# EDA-Robot_V1_3.net
KiCad netlist of a schematic drawn in EasyEDA Pro
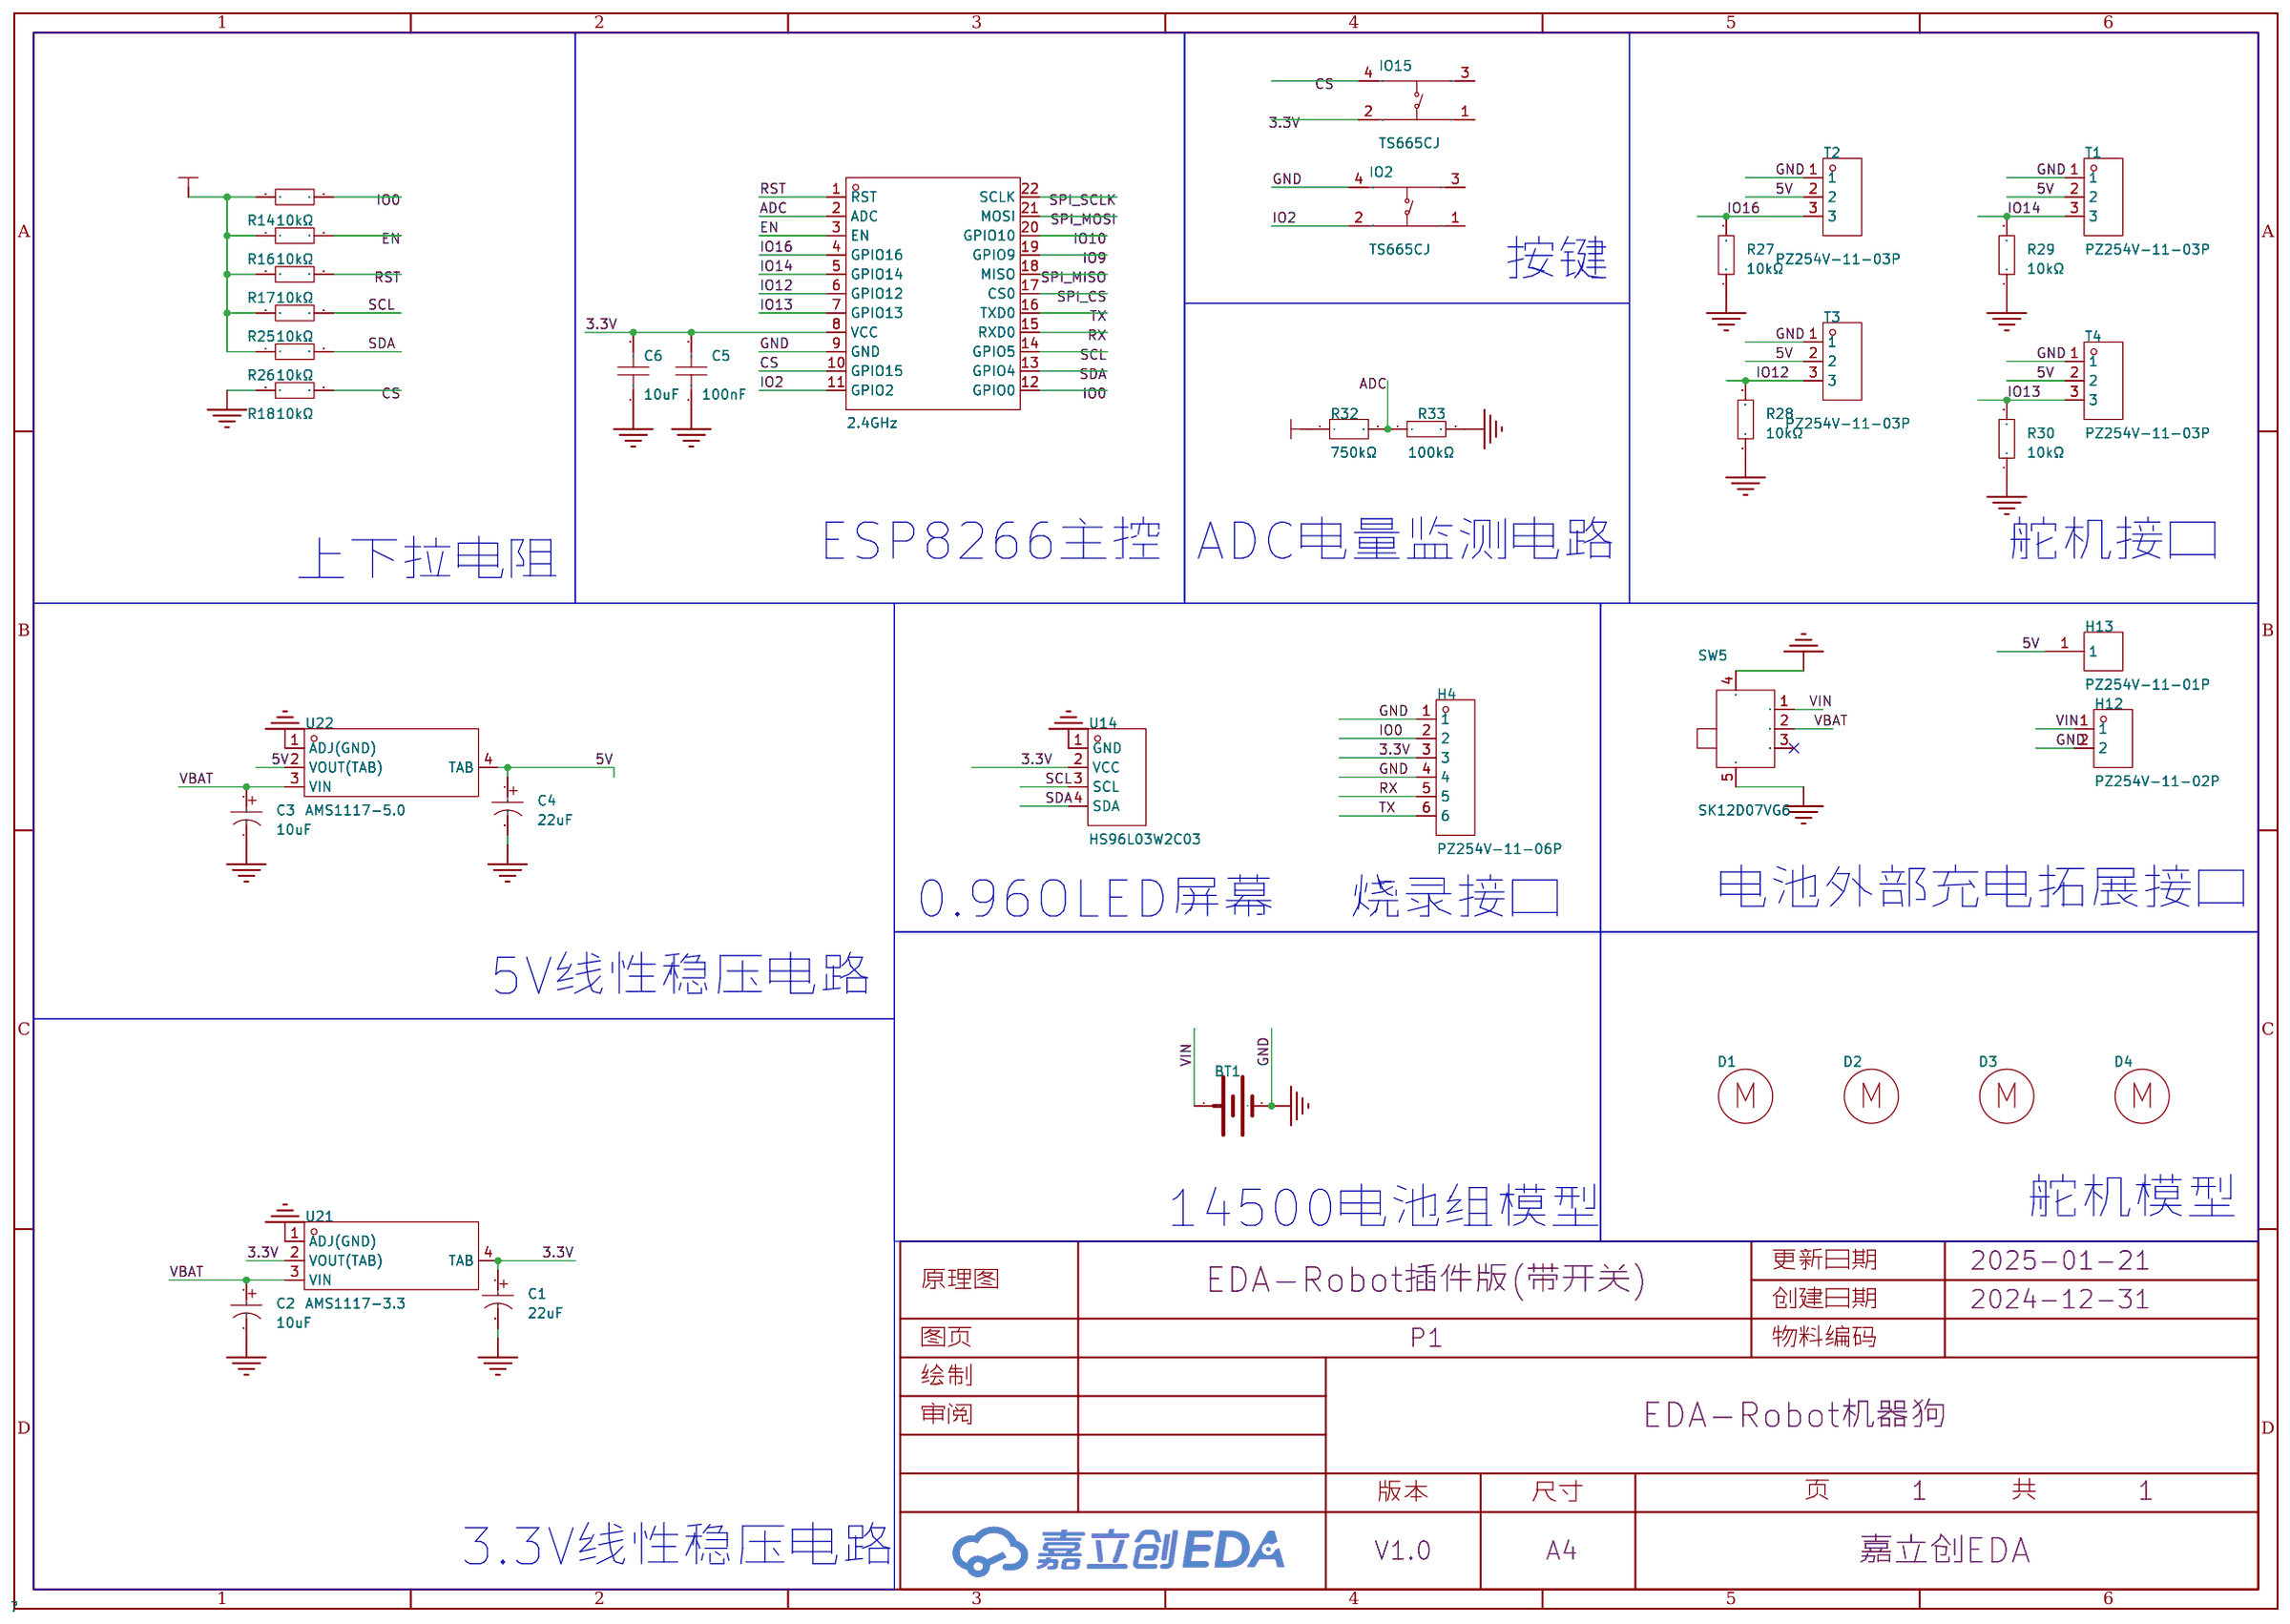
[diagram p0: schematic sheet]

(export (version "E")
  (design (tool "Eeschema 10.0.6"))
  (components
    (comp (ref "BT1")
      (value "~")
      (footprint "easyedapro:14500电池盒*2")
      (description "连接器类型:电池底座;适用电池规格:CR1220;触头材质:磷青铜;工作温度范围:-25°C~+85°C;")
      (libsource (lib "easyedapro") (part "2节串联14500电池组"))
    )
    (comp (ref "C1")
      (value "22uF")
      (footprint "easyedapro:CAP-TH_BD4.0-P1.50-D0.8-FD")
      (description "容值:10uF;精度:±20%;额定电压:25V;纹波电流:29mA@120Hz;等效串联电阻:-;")
      (fields
        (field (name "Manufacturer Part") "KS226M025C07RR0VH2FP0")
        (field (name "Manufacturer") "CX(承兴)")
      )
      (libsource (lib "easyedapro") (part "10uF 25V 4*7"))
    )
    (comp (ref "C2")
      (value "10uF")
      (footprint "easyedapro:CAP-TH_BD4.0-P1.50-D0.8-FD")
      (description "容值:10uF;精度:±20%;额定电压:25V;纹波电流:29mA@120Hz;等效串联电阻:-;")
      (fields
        (field (name "Manufacturer Part") "KS106M025C07RR0VH2FP0")
        (field (name "Manufacturer") "CX(承兴)")
      )
      (libsource (lib "easyedapro") (part "10uF 25V 4*7"))
    )
    (comp (ref "C3")
      (value "10uF")
      (footprint "easyedapro:CAP-TH_BD4.0-P1.50-D0.8-FD")
      (description "容值:10uF;精度:±20%;额定电压:25V;纹波电流:29mA@120Hz;等效串联电阻:-;")
      (fields
        (field (name "Manufacturer Part") "KS106M025C07RR0VH2FP0")
        (field (name "Manufacturer") "CX(承兴)")
      )
      (libsource (lib "easyedapro") (part "10uF 25V 4*7"))
    )
    (comp (ref "C4")
      (value "22uF")
      (footprint "easyedapro:CAP-TH_BD4.0-P1.50-D0.8-FD")
      (description "容值:22uF;精度:±20%;额定电压:25V;纹波电流:-;等效串联电阻:-;")
      (fields
        (field (name "Manufacturer Part") "KS226M025C07RR0VH2FP0")
        (field (name "Manufacturer") "CX(承兴)")
      )
      (libsource (lib "easyedapro") (part "22uF 25V 4*7"))
    )
    (comp (ref "C5")
      (value "100nF")
      (footprint "easyedapro:CAP-TH_L4.2-W3.5-P2.54-D0.5")
      (description "容值:100nF;精度:±10%;额定电压:50V;温度系数:X7R;")
      (fields (field (name "Manufacturer Part") "178MU0006") (field (name "Manufacturer") "KNSCHA(科尼盛)"))
      (libsource (lib "easyedapro") (part "178MU0006"))
    )
    (comp (ref "C6")
      (value "10uF")
      (footprint "easyedapro:CAP-TH_L5.5-W3.8-P3.50-D0.6")
      (description "容值:10uF;精度:±20%;额定电压:25V;温度系数:X5R;")
      (fields
        (field (name "Manufacturer Part") "CD1E106MC9BER2F100")
        (field (name "Manufacturer") "Dersonic(德尔创)")
      )
      (libsource (lib "easyedapro") (part "CD1E106MC9BER2F100"))
    )
    (comp (ref "D1")
      (value "~")
      (footprint "easyedapro:舵机")
      (libsource (lib "easyedapro") (part "SG90舵机(180度版)"))
    )
    (comp (ref "D2")
      (value "~")
      (footprint "easyedapro:舵机")
      (libsource (lib "easyedapro") (part "SG90舵机(180度版)"))
    )
    (comp (ref "D3")
      (value "~")
      (footprint "easyedapro:舵机")
      (libsource (lib "easyedapro") (part "SG90舵机(180度版)"))
    )
    (comp (ref "D4")
      (value "~")
      (footprint "easyedapro:舵机")
      (libsource (lib "easyedapro") (part "SG90舵机(180度版)"))
    )
    (comp (ref "H4")
      (value "PZ254V-11-06P")
      (footprint "easyedapro:HDR-TH_6P-P2.54-V-M")
      (fields (field (name "Manufacturer") "XFCN(兴飞)"))
      (libsource (lib "easyedapro") (part "PZ254V-11-06P"))
    )
    (comp (ref "H12")
      (value "PZ254V-11-02P")
      (footprint "easyedapro:HDR-TH_2P-P2.54-V-M")
      (fields (field (name "Manufacturer") "XFCN(兴飞)"))
      (libsource (lib "easyedapro") (part "PZ254V-11-02P"))
    )
    (comp (ref "H13")
      (value "PZ254V-11-01P")
      (footprint "easyedapro:HDR-TH_1P-P2.54-V-M")
      (fields (field (name "Manufacturer") "XFCN(兴飞)"))
      (libsource (lib "easyedapro") (part "PZ254V-11-01P"))
    )
    (comp (ref "IO2")
      (value "TS665CJ")
      (footprint "easyedapro:SW-TH_4P-L6.0-W6.0-P4.50-LS6.5")
      (description "电路结构:单刀单掷;按钮形状:圆形按钮;安装方式:直插;开关长度:6mm;开关宽度:6mm;开关高度:5mm;触点电流:50mA;额定电压(DC):12V;带灯:-;机械寿命:-;")
      (fields (field (name "Manufacturer") "SHOU HAN(首韩)"))
      (libsource (lib "easyedapro") (part "TS665CJ"))
    )
    (comp (ref "IO15")
      (value "TS665CJ")
      (footprint "easyedapro:SW-TH_4P-L6.0-W6.0-P4.50-LS6.5")
      (description "电路结构:单刀单掷;按钮形状:圆形按钮;安装方式:直插;开关长度:6mm;开关宽度:6mm;开关高度:5mm;触点电流:50mA;额定电压(DC):12V;带灯:-;机械寿命:-;")
      (fields (field (name "Manufacturer") "SHOU HAN(首韩)"))
      (libsource (lib "easyedapro") (part "TS665CJ"))
    )
    (comp (ref "R14")
      (value "10kΩ")
      (footprint "easyedapro:R0805")
      (description "电阻类型:厚膜电阻;阻值:10kΩ;精度:±5%;功率:125mW;最大工作电压:150V;温度系数:±100ppm/°C;")
      (fields
        (field (name "Manufacturer Part") "RN1/4W10KFT/BA1")
        (field (name "Manufacturer") "Tyohm(幸亚电阻)")
      )
      (libsource (lib "easyedapro") (part "0805W8J0103T5E"))
    )
    (comp (ref "R16")
      (value "10kΩ")
      (footprint "easyedapro:R0805")
      (description "电阻类型:厚膜电阻;阻值:10kΩ;精度:±5%;功率:125mW;最大工作电压:150V;温度系数:±100ppm/°C;")
      (fields
        (field (name "Manufacturer Part") "RN1/4W10KFT/BA1")
        (field (name "Manufacturer") "Tyohm(幸亚电阻)")
      )
      (libsource (lib "easyedapro") (part "0805W8J0103T5E"))
    )
    (comp (ref "R17")
      (value "10kΩ")
      (footprint "easyedapro:R0805")
      (description "电阻类型:厚膜电阻;阻值:10kΩ;精度:±5%;功率:125mW;最大工作电压:150V;温度系数:±100ppm/°C;")
      (fields
        (field (name "Manufacturer Part") "RN1/4W10KFT/BA1")
        (field (name "Manufacturer") "Tyohm(幸亚电阻)")
      )
      (libsource (lib "easyedapro") (part "0805W8J0103T5E"))
    )
    (comp (ref "R18")
      (value "10kΩ")
      (footprint "easyedapro:R0805")
      (description "电阻类型:厚膜电阻;阻值:10kΩ;精度:±5%;功率:125mW;最大工作电压:150V;温度系数:±100ppm/°C;")
      (fields
        (field (name "Manufacturer Part") "RN1/4W10KFT/BA1")
        (field (name "Manufacturer") "Tyohm(幸亚电阻)")
      )
      (libsource (lib "easyedapro") (part "0805W8J0103T5E"))
    )
    (comp (ref "R25")
      (value "10kΩ")
      (footprint "easyedapro:R0805")
      (description "电阻类型:厚膜电阻;阻值:10kΩ;精度:±5%;功率:125mW;最大工作电压:150V;温度系数:±100ppm/°C;")
      (fields
        (field (name "Manufacturer Part") "RN1/4W10KFT/BA1")
        (field (name "Manufacturer") "Tyohm(幸亚电阻)")
      )
      (libsource (lib "easyedapro") (part "0805W8J0103T5E"))
    )
    (comp (ref "R26")
      (value "10kΩ")
      (footprint "easyedapro:R0805")
      (description "电阻类型:厚膜电阻;阻值:10kΩ;精度:±5%;功率:125mW;最大工作电压:150V;温度系数:±100ppm/°C;")
      (fields
        (field (name "Manufacturer Part") "RN1/4W10KFT/BA1")
        (field (name "Manufacturer") "Tyohm(幸亚电阻)")
      )
      (libsource (lib "easyedapro") (part "0805W8J0103T5E"))
    )
    (comp (ref "R27")
      (value "10kΩ")
      (footprint "easyedapro:R0805")
      (description "电阻类型:厚膜电阻;阻值:10kΩ;精度:±5%;功率:125mW;最大工作电压:150V;温度系数:±100ppm/°C;")
      (fields
        (field (name "Manufacturer Part") "RN1/4W10KFT/BA1")
        (field (name "Manufacturer") "Tyohm(幸亚电阻)")
      )
      (libsource (lib "easyedapro") (part "0805W8J0103T5E"))
    )
    (comp (ref "R28")
      (value "10kΩ")
      (footprint "easyedapro:R0805")
      (description "电阻类型:厚膜电阻;阻值:10kΩ;精度:±5%;功率:125mW;最大工作电压:150V;温度系数:±100ppm/°C;")
      (fields
        (field (name "Manufacturer Part") "RN1/4W10KFT/BA1")
        (field (name "Manufacturer") "Tyohm(幸亚电阻)")
      )
      (libsource (lib "easyedapro") (part "0805W8J0103T5E"))
    )
    (comp (ref "R29")
      (value "10kΩ")
      (footprint "easyedapro:R0805")
      (description "电阻类型:厚膜电阻;阻值:10kΩ;精度:±5%;功率:125mW;最大工作电压:150V;温度系数:±100ppm/°C;")
      (fields
        (field (name "Manufacturer Part") "RN1/4W10KFT/BA1")
        (field (name "Manufacturer") "Tyohm(幸亚电阻)")
      )
      (libsource (lib "easyedapro") (part "0805W8J0103T5E"))
    )
    (comp (ref "R30")
      (value "10kΩ")
      (footprint "easyedapro:R0805")
      (description "电阻类型:厚膜电阻;阻值:10kΩ;精度:±5%;功率:125mW;最大工作电压:150V;温度系数:±100ppm/°C;")
      (fields
        (field (name "Manufacturer Part") "RN1/4W10KFT/BA1")
        (field (name "Manufacturer") "Tyohm(幸亚电阻)")
      )
      (libsource (lib "easyedapro") (part "0805W8J0103T5E"))
    )
    (comp (ref "R32")
      (value "750kΩ")
      (footprint "easyedapro:RES-TH_BD2.4-L6.3-P10.30-D0.6")
      (description "电阻类型:金属膜电阻;阻值:75Ω;精度:±1%;功率:250mW;温度系数:±50ppm/°C;")
      (fields (field (name "Manufacturer Part") "MFR-25FTE52-750K") (field (name "Manufacturer") "YAGEO(国巨)"))
      (libsource (lib "easyedapro") (part "MFR-25FTE52-75R"))
    )
    (comp (ref "R33")
      (value "100kΩ")
      (footprint "easyedapro:R0805")
      (description "电阻类型:厚膜电阻;阻值:10kΩ;精度:±5%;功率:125mW;最大工作电压:150V;温度系数:±100ppm/°C;")
      (fields (field (name "Manufacturer Part") "MFR50SFTE52-100K") (field (name "Manufacturer") "YAGEO(国巨)"))
      (libsource (lib "easyedapro") (part "0805W8J0103T5E"))
    )
    (comp (ref "SW5")
      (value "SK12D07VG6")
      (footprint "easyedapro:SW-TH_SK12D07VG6")
      (description "电路结构:单刀双掷;安装方式:-;开关颜色:-;额定电流(DC):500mA;额定电压(DC):50V;额定电流(AC):-;额定电压(AC):-;机械寿命:5千次;")
      (fields (field (name "Manufacturer") "SHOU HAN(首韩)"))
      (libsource (lib "easyedapro") (part "SK12D07VG6"))
    )
    (comp (ref "T1")
      (value "PZ254V-11-03P")
      (fields (field (name "Manufacturer") "XFCN(兴飞)"))
      (libsource (lib "easyedapro") (part "PZ254V-11-03P_C2937625"))
    )
    (comp (ref "T2")
      (value "PZ254V-11-03P")
      (fields (field (name "Manufacturer") "XFCN(兴飞)"))
      (libsource (lib "easyedapro") (part "PZ254V-11-03P_C2937625"))
    )
    (comp (ref "T3")
      (value "PZ254V-11-03P")
      (fields (field (name "Manufacturer") "XFCN(兴飞)"))
      (libsource (lib "easyedapro") (part "PZ254V-11-03P_C2937625"))
    )
    (comp (ref "T4")
      (value "PZ254V-11-03P")
      (fields (field (name "Manufacturer") "XFCN(兴飞)"))
      (libsource (lib "easyedapro") (part "PZ254V-11-03P_C2937625"))
    )
    (comp (ref "U10")
      (value "2.4GHz")
      (fields
        (field (name "Manufacturer Part") "ESP-12F(ESP8266MOD)")
        (field (name "Manufacturer") "Ai-Thinker(安信可)")
      )
      (libsource (lib "easyedapro") (part "ESP-12F(ESP8266MOD)"))
    )
    (comp (ref "U14")
      (value "HS96L03W2C03")
      (footprint "easyedapro:OLED-TH_L27.8-W27.2-P2.54_C9900033791")
      (description "主控芯片:SSD1315;接口类型:I2C;尺寸(inch):0.96;像素分辨率:128x64;")
      (fields (field (name "Manufacturer") "HS(汉昇)"))
      (libsource (lib "easyedapro") (part "HS96L03W2C03"))
    )
    (comp (ref "U21")
      (value "AMS1117-3.3")
      (fields (field (name "Manufacturer") "UMW(友台半导体)"))
      (libsource (lib "easyedapro") (part "AMS1117-3.3_C347222"))
    )
    (comp (ref "U22")
      (value "AMS1117-5.0")
      (fields (field (name "Manufacturer") "UMW(友台半导体)"))
      (libsource (lib "easyedapro") (part "AMS1117-5.0_C347223"))
    )
  )
  (nets
    (net (code "1") (name "/5V") (class "Default")
      (node (ref "C4") (pin "1") (pinfunction "1_1") (pintype "input"))
      (node (ref "H13") (pin "1") (pinfunction "1_1") (pintype "unspecified"))
      (node (ref "T1") (pin "2") (pinfunction "2_2") (pintype "unspecified"))
      (node (ref "T2") (pin "2") (pinfunction "2_2") (pintype "unspecified"))
      (node (ref "T3") (pin "2") (pinfunction "2_2") (pintype "unspecified"))
      (node (ref "T4") (pin "2") (pinfunction "2_2") (pintype "unspecified"))
      (node (ref "U22") (pin "2") (pinfunction "VOUT(TAB)_2") (pintype "unspecified"))
      (node (ref "U22") (pin "4") (pinfunction "TAB_4") (pintype "unspecified"))
    )
    (net (code "2") (name "/ADC") (class "Default")
      (node (ref "R32") (pin "2") (pinfunction "2_2") (pintype "unspecified"))
      (node (ref "R33") (pin "1") (pinfunction "1_1") (pintype "input"))
      (node (ref "U10") (pin "2") (pinfunction "ADC_2") (pintype "unspecified"))
    )
    (net (code "3") (name "/CS") (class "Default")
      (node (ref "IO15") (pin "4") (pinfunction "D_4") (pintype "unspecified"))
      (node (ref "R18") (pin "2") (pinfunction "2_2") (pintype "input"))
      (node (ref "U10") (pin "10") (pinfunction "GPIO15_10") (pintype "unspecified"))
    )
    (net (code "4") (name "/EN") (class "Default")
      (node (ref "R16") (pin "2") (pinfunction "2_2") (pintype "input"))
      (node (ref "U10") (pin "3") (pinfunction "EN_3") (pintype "unspecified"))
    )
    (net (code "5") (name "/IO0") (class "Default")
      (node (ref "H4") (pin "2") (pinfunction "2_2") (pintype "unspecified"))
      (node (ref "R14") (pin "2") (pinfunction "2_2") (pintype "input"))
      (node (ref "U10") (pin "12") (pinfunction "GPIO0_12") (pintype "unspecified"))
    )
    (net (code "6") (name "/IO2") (class "Default")
      (node (ref "IO2") (pin "2") (pinfunction "B_2") (pintype "unspecified"))
      (node (ref "U10") (pin "11") (pinfunction "GPIO2_11") (pintype "unspecified"))
    )
    (net (code "7") (name "/IO9") (class "Default")
      (node (ref "U10") (pin "19") (pinfunction "GPIO9_19") (pintype "unspecified"))
    )
    (net (code "8") (name "/IO10") (class "Default")
      (node (ref "U10") (pin "20") (pinfunction "GPIO10_20") (pintype "unspecified"))
    )
    (net (code "9") (name "/IO12") (class "Default")
      (node (ref "R28") (pin "2") (pinfunction "2_2") (pintype "input"))
      (node (ref "T3") (pin "3") (pinfunction "3_3") (pintype "unspecified"))
      (node (ref "U10") (pin "6") (pinfunction "GPIO12_6") (pintype "unspecified"))
    )
    (net (code "10") (name "/IO13") (class "Default")
      (node (ref "R30") (pin "2") (pinfunction "2_2") (pintype "input"))
      (node (ref "T4") (pin "3") (pinfunction "3_3") (pintype "unspecified"))
      (node (ref "U10") (pin "7") (pinfunction "GPIO13_7") (pintype "unspecified"))
    )
    (net (code "11") (name "/IO14") (class "Default")
      (node (ref "R29") (pin "2") (pinfunction "2_2") (pintype "input"))
      (node (ref "T1") (pin "3") (pinfunction "3_3") (pintype "unspecified"))
      (node (ref "U10") (pin "5") (pinfunction "GPIO14_5") (pintype "unspecified"))
    )
    (net (code "12") (name "/IO16") (class "Default")
      (node (ref "R27") (pin "2") (pinfunction "2_2") (pintype "input"))
      (node (ref "T2") (pin "3") (pinfunction "3_3") (pintype "unspecified"))
      (node (ref "U10") (pin "4") (pinfunction "GPIO16_4") (pintype "unspecified"))
    )
    (net (code "13") (name "/RST") (class "Default")
      (node (ref "R17") (pin "2") (pinfunction "2_2") (pintype "input"))
      (node (ref "U10") (pin "1") (pinfunction "RST_1") (pintype "unspecified"))
    )
    (net (code "14") (name "/RX") (class "Default")
      (node (ref "H4") (pin "5") (pinfunction "5_5") (pintype "unspecified"))
      (node (ref "U10") (pin "15") (pinfunction "RXD0_15") (pintype "unspecified"))
    )
    (net (code "15") (name "/SCL") (class "Default")
      (node (ref "R25") (pin "2") (pinfunction "2_2") (pintype "input"))
      (node (ref "U10") (pin "14") (pinfunction "GPIO5_14") (pintype "unspecified"))
      (node (ref "U14") (pin "3") (pinfunction "SCL_3") (pintype "unspecified"))
    )
    (net (code "16") (name "/SDA") (class "Default")
      (node (ref "R26") (pin "2") (pinfunction "2_2") (pintype "input"))
      (node (ref "U10") (pin "13") (pinfunction "GPIO4_13") (pintype "unspecified"))
      (node (ref "U14") (pin "4") (pinfunction "SDA_4") (pintype "unspecified"))
    )
    (net (code "17") (name "/SPI_CS") (class "Default")
      (node (ref "U10") (pin "17") (pinfunction "CS0_17") (pintype "unspecified"))
    )
    (net (code "18") (name "/SPI_MISO") (class "Default")
      (node (ref "U10") (pin "18") (pinfunction "MISO_18") (pintype "unspecified"))
    )
    (net (code "19") (name "/SPI_MOSI") (class "Default")
      (node (ref "U10") (pin "21") (pinfunction "MOSI_21") (pintype "unspecified"))
    )
    (net (code "20") (name "/SPI_SCLK") (class "Default")
      (node (ref "U10") (pin "22") (pinfunction "SCLK_22") (pintype "unspecified"))
    )
    (net (code "21") (name "/TX") (class "Default")
      (node (ref "H4") (pin "6") (pinfunction "6_6") (pintype "unspecified"))
      (node (ref "U10") (pin "16") (pinfunction "TXD0_16") (pintype "unspecified"))
    )
    (net (code "22") (name "/VIN") (class "Default")
      (node (ref "BT1") (pin "1") (pinfunction "+_1") (pintype "unspecified"))
      (node (ref "H12") (pin "1") (pinfunction "1_1") (pintype "unspecified"))
      (node (ref "SW5") (pin "1") (pinfunction "1_1") (pintype "unspecified"))
    )
    (net (code "23") (name "3.3V") (class "Default")
      (node (ref "C1") (pin "1") (pinfunction "1_1") (pintype "input"))
      (node (ref "C5") (pin "2") (pinfunction "2_2") (pintype "unspecified"))
      (node (ref "C6") (pin "2") (pinfunction "2_2") (pintype "unspecified"))
      (node (ref "H4") (pin "3") (pinfunction "3_3") (pintype "unspecified"))
      (node (ref "IO15") (pin "2") (pinfunction "B_2") (pintype "unspecified"))
      (node (ref "R14") (pin "1") (pinfunction "1_1") (pintype "input"))
      (node (ref "R16") (pin "1") (pinfunction "1_1") (pintype "input"))
      (node (ref "R17") (pin "1") (pinfunction "1_1") (pintype "input"))
      (node (ref "R25") (pin "1") (pinfunction "1_1") (pintype "input"))
      (node (ref "R26") (pin "1") (pinfunction "1_1") (pintype "input"))
      (node (ref "U10") (pin "8") (pinfunction "VCC_8") (pintype "unspecified"))
      (node (ref "U14") (pin "2") (pinfunction "VCC_2") (pintype "unspecified"))
      (node (ref "U21") (pin "2") (pinfunction "VOUT(TAB)_2") (pintype "unspecified"))
      (node (ref "U21") (pin "4") (pinfunction "TAB_4") (pintype "unspecified"))
    )
    (net (code "24") (name "GND") (class "Default")
      (node (ref "BT1") (pin "2") (pinfunction "-_2") (pintype "unspecified"))
      (node (ref "C1") (pin "2") (pinfunction "2_2") (pintype "input"))
      (node (ref "C2") (pin "2") (pinfunction "2_2") (pintype "input"))
      (node (ref "C3") (pin "2") (pinfunction "2_2") (pintype "input"))
      (node (ref "C4") (pin "2") (pinfunction "2_2") (pintype "input"))
      (node (ref "C5") (pin "1") (pinfunction "1_1") (pintype "unspecified"))
      (node (ref "C6") (pin "1") (pinfunction "1_1") (pintype "unspecified"))
      (node (ref "H12") (pin "2") (pinfunction "2_2") (pintype "unspecified"))
      (node (ref "H4") (pin "1") (pinfunction "1_1") (pintype "unspecified"))
      (node (ref "H4") (pin "4") (pinfunction "4_4") (pintype "unspecified"))
      (node (ref "IO2") (pin "4") (pinfunction "D_4") (pintype "unspecified"))
      (node (ref "R18") (pin "1") (pinfunction "1_1") (pintype "input"))
      (node (ref "R27") (pin "1") (pinfunction "1_1") (pintype "input"))
      (node (ref "R28") (pin "1") (pinfunction "1_1") (pintype "input"))
      (node (ref "R29") (pin "1") (pinfunction "1_1") (pintype "input"))
      (node (ref "R30") (pin "1") (pinfunction "1_1") (pintype "input"))
      (node (ref "R33") (pin "2") (pinfunction "2_2") (pintype "input"))
      (node (ref "SW5") (pin "4") (pinfunction "4_4") (pintype "unspecified"))
      (node (ref "SW5") (pin "5") (pinfunction "5_5") (pintype "unspecified"))
      (node (ref "T1") (pin "1") (pinfunction "1_1") (pintype "unspecified"))
      (node (ref "T2") (pin "1") (pinfunction "1_1") (pintype "unspecified"))
      (node (ref "T3") (pin "1") (pinfunction "1_1") (pintype "unspecified"))
      (node (ref "T4") (pin "1") (pinfunction "1_1") (pintype "unspecified"))
      (node (ref "U10") (pin "9") (pinfunction "GND_9") (pintype "unspecified"))
      (node (ref "U14") (pin "1") (pinfunction "GND_1") (pintype "unspecified"))
      (node (ref "U21") (pin "1") (pinfunction "ADJ(GND)_1") (pintype "unspecified"))
      (node (ref "U22") (pin "1") (pinfunction "ADJ(GND)_1") (pintype "unspecified"))
    )
    (net (code "25") (name "VBAT") (class "Default")
      (node (ref "C2") (pin "1") (pinfunction "1_1") (pintype "input"))
      (node (ref "C3") (pin "1") (pinfunction "1_1") (pintype "input"))
      (node (ref "R32") (pin "1") (pinfunction "1_1") (pintype "unspecified"))
      (node (ref "SW5") (pin "2") (pinfunction "2_2") (pintype "unspecified"))
      (node (ref "U21") (pin "3") (pinfunction "VIN_3") (pintype "unspecified"))
      (node (ref "U22") (pin "3") (pinfunction "VIN_3") (pintype "unspecified"))
    )
    (net (code "26") (name "unconnected-(IO2-A-Pad1)") (class "Default")
      (node (ref "IO2") (pin "1") (pinfunction "A_1") (pintype "unspecified"))
    )
    (net (code "27") (name "unconnected-(IO2-C-Pad3)") (class "Default")
      (node (ref "IO2") (pin "3") (pinfunction "C_3") (pintype "unspecified"))
    )
    (net (code "28") (name "unconnected-(IO15-A-Pad1)") (class "Default")
      (node (ref "IO15") (pin "1") (pinfunction "A_1") (pintype "unspecified"))
    )
    (net (code "29") (name "unconnected-(IO15-C-Pad3)") (class "Default")
      (node (ref "IO15") (pin "3") (pinfunction "C_3") (pintype "unspecified"))
    )
    (net (code "30") (name "unconnected-(SW5-Pad3)") (class "Default")
      (node (ref "SW5") (pin "3") (pinfunction "3_3") (pintype "unspecified+no_connect"))
    )
  )
)
